# sim800.net
KiCad netlist of a schematic drawn in EAGLE
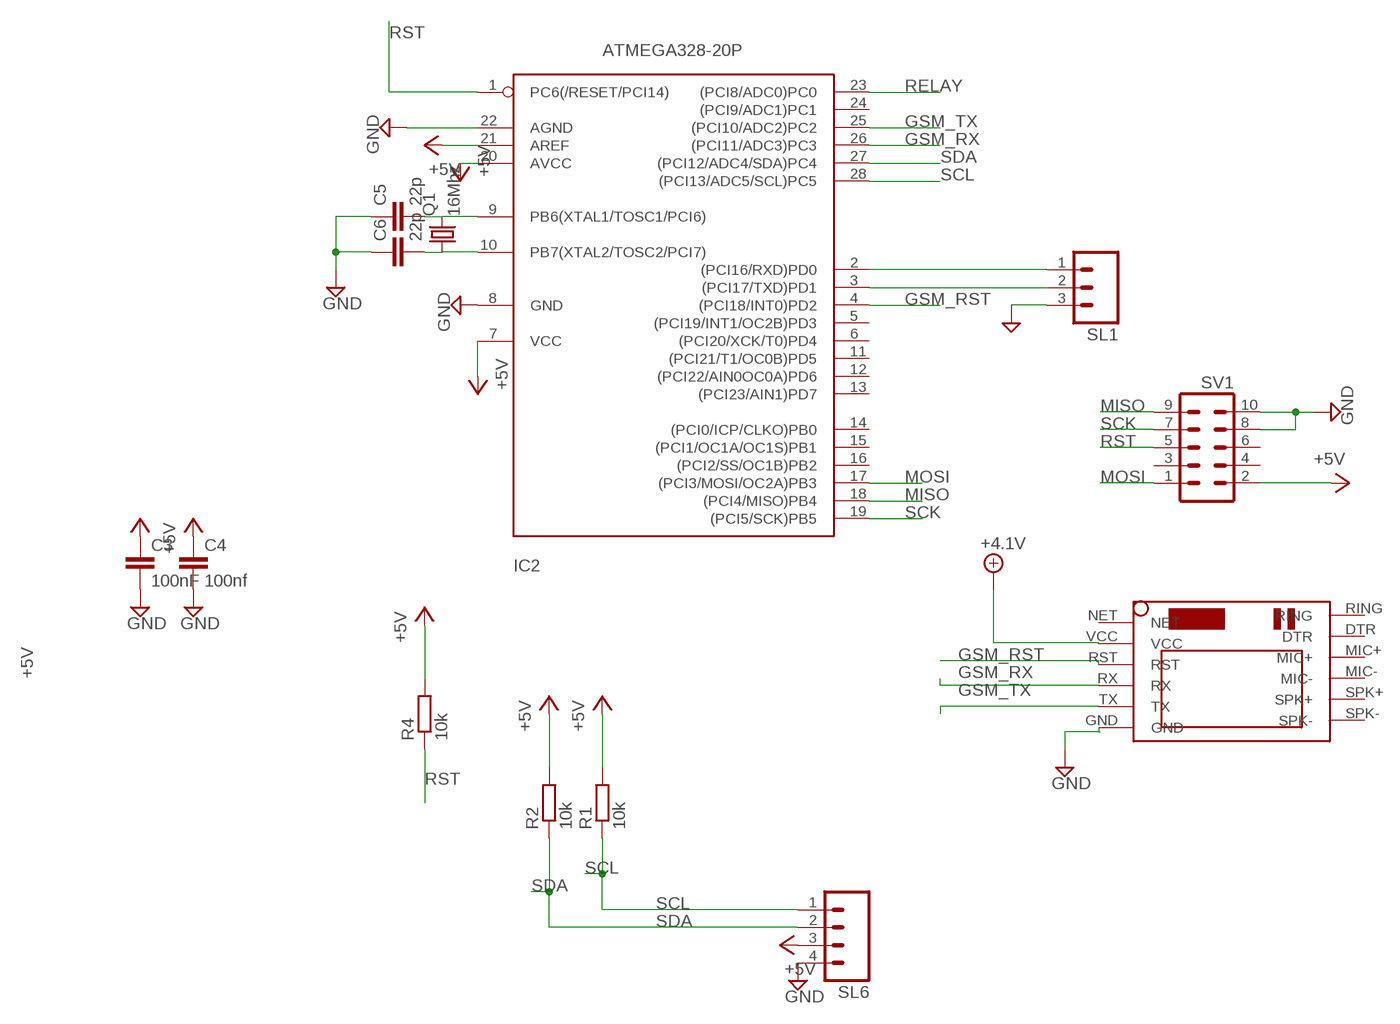
[diagram p0: schematic, sheet 1]
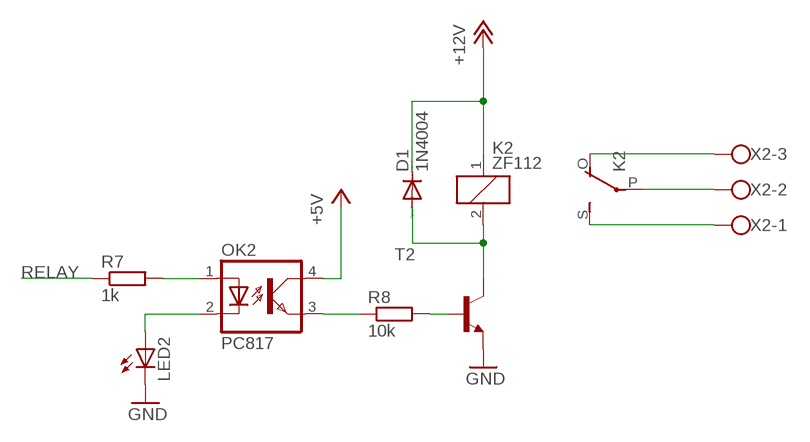
[diagram p1: schematic, sheet 2]
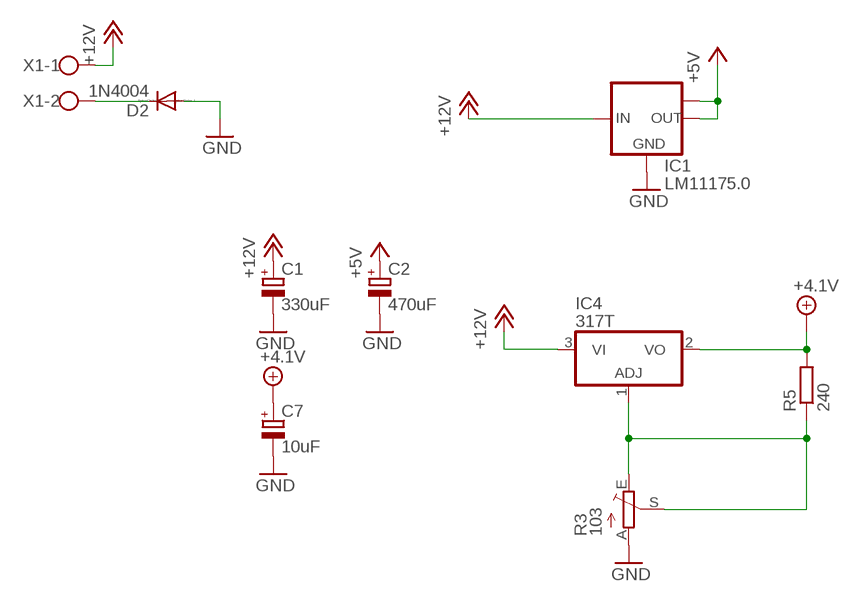
[diagram p2: schematic, sheet 3]

(export (version "E")
  (design (tool "Eeschema 10.0.6"))
  (components
    (comp (ref "C1")
      (value "330uF")
      (footprint "eagle-import:E3,5-8")
      (libsource (lib "eagle-import") (part "CPOL-EUE3.5-8"))
    )
    (comp (ref "C2")
      (value "470uF")
      (footprint "eagle-import:E3,5-8")
      (libsource (lib "eagle-import") (part "CPOL-EUE3.5-8"))
    )
    (comp (ref "C7")
      (value "10uF")
      (footprint "eagle-import:E2,5-6")
      (libsource (lib "eagle-import") (part "CPOL-EUE2.5-6"))
    )
    (comp (ref "D2")
      (value "1N4004")
      (footprint "eagle-import:DO41-10")
      (libsource (lib "eagle-import") (part "1N4004"))
    )
    (comp (ref "IC1")
      (value "LM11175.0")
      (footprint "eagle-import:SOT223")
      (libsource (lib "eagle-import") (part "LM1117MPX-5.0"))
    )
    (comp (ref "IC4")
      (value "317T")
      (footprint "eagle-import:TO220H")
      (libsource (lib "eagle-import") (part "317T"))
    )
    (comp (ref "R3")
      (value "103")
      (footprint "eagle-import:CA6V")
      (libsource (lib "eagle-import") (part "TRIM_EU-CA6V"))
    )
    (comp (ref "R5")
      (value "240")
      (footprint "eagle-import:0207_10")
      (libsource (lib "eagle-import") (part "R-EU_0207/10"))
    )
    (comp (ref "X1")
      (value "W237-102")
      (footprint "eagle-import:W237-102")
      (fields (field (name "MPN") "237-102"))
      (libsource (lib "eagle-import") (part "W237-102"))
    )
    (comp (ref "D1")
      (value "1N4004")
      (footprint "eagle-import:DO41-10")
      (libsource (lib "eagle-import") (part "1N4004"))
    )
    (comp (ref "K2")
      (value "ZF112")
      (footprint "eagle-import:ZF112")
      (libsource (lib "eagle-import") (part "ZF112"))
    )
    (comp (ref "LED2")
      (value "LED3MM")
      (footprint "eagle-import:LED3MM")
      (libsource (lib "eagle-import") (part "LED3MM"))
    )
    (comp (ref "OK2")
      (value "PC817")
      (footprint "eagle-import:DIL04")
      (fields (field (name "MPN") "PC817X4J000F"))
      (libsource (lib "eagle-import") (part "PC817"))
    )
    (comp (ref "R7")
      (value "1k")
      (footprint "eagle-import:0207_10")
      (libsource (lib "eagle-import") (part "R-EU_0207/10"))
    )
    (comp (ref "R8")
      (value "10k")
      (footprint "eagle-import:0207_10")
      (libsource (lib "eagle-import") (part "R-EU_0207/10"))
    )
    (comp (ref "T2")
      (value "-NPN-TO92-EBC")
      (footprint "eagle-import:TO92-EBC")
      (libsource (lib "eagle-import") (part "-NPN-TO92-EBC"))
    )
    (comp (ref "X2")
      (value "W237-103")
      (footprint "eagle-import:W237-103")
      (fields (field (name "MPN") "237-103"))
      (libsource (lib "eagle-import") (part "W237-103"))
    )
    (comp (ref "C3")
      (value "100nF")
      (footprint "eagle-import:C050-025X075")
      (libsource (lib "eagle-import") (part "C-EU050-025X075"))
    )
    (comp (ref "C4")
      (value "100nf")
      (footprint "eagle-import:C050-025X075")
      (libsource (lib "eagle-import") (part "C-EU050-025X075"))
    )
    (comp (ref "C5")
      (value "22p")
      (footprint "eagle-import:C025-025X050")
      (libsource (lib "eagle-import") (part "C-EU025-025X050"))
    )
    (comp (ref "C6")
      (value "22p")
      (footprint "eagle-import:C025-025X050")
      (libsource (lib "eagle-import") (part "C-EU025-025X050"))
    )
    (comp (ref "IC2")
      (value "ATMEGA328-20P")
      (footprint "eagle-import:DIL28-3")
      (libsource (lib "eagle-import") (part "ATMEGA328P-20"))
    )
    (comp (ref "Q1")
      (value "16Mhz")
      (footprint "eagle-import:HC49U-V")
      (libsource (lib "eagle-import") (part "CRYSTALHC49U-V"))
    )
    (comp (ref "R1")
      (value "10k")
      (footprint "eagle-import:0207_10")
      (libsource (lib "eagle-import") (part "R-EU_0207/10"))
    )
    (comp (ref "R2")
      (value "10k")
      (footprint "eagle-import:0207_10")
      (libsource (lib "eagle-import") (part "R-EU_0207/10"))
    )
    (comp (ref "R4")
      (value "10k")
      (footprint "eagle-import:0207_10")
      (libsource (lib "eagle-import") (part "R-EU_0207/10"))
    )
    (comp (ref "SL1")
      (value "M03")
      (footprint "eagle-import:03P")
      (libsource (lib "eagle-import") (part "M03"))
    )
    (comp (ref "SL6")
      (value "M04")
      (footprint "eagle-import:04P")
      (libsource (lib "eagle-import") (part "M04"))
    )
    (comp (ref "SV1")
      (value "ML10")
      (footprint "eagle-import:ML10")
      (libsource (lib "eagle-import") (part "ML10"))
    )
    (comp (ref "U$1")
      (value "SIM800LMODULE")
      (footprint "eagle-import:SIM800LMODULE")
      (libsource (lib "eagle-import") (part "SIM800LMODULE"))
    )
  )
  (nets
    (net (code "1") (name "+4.1V") (class "Default")
      (node (ref "C7") (pin "+") (pinfunction "+_+") (pintype "passive"))
      (node (ref "IC4") (pin "2") (pinfunction "VO_2") (pintype "passive"))
      (node (ref "R5") (pin "2") (pinfunction "2_2") (pintype "passive"))
      (node (ref "U$1") (pin "VCC") (pinfunction "VCC_VCC") (pintype "bidirectional"))
    )
    (net (code "2") (name "+5V") (class "Default")
      (node (ref "C2") (pin "+") (pinfunction "+_+") (pintype "passive"))
      (node (ref "C3") (pin "1") (pinfunction "1_1") (pintype "passive"))
      (node (ref "C4") (pin "1") (pinfunction "1_1") (pintype "passive"))
      (node (ref "IC1") (pin "2") (pinfunction "OUT_2") (pintype "passive"))
      (node (ref "IC1") (pin "TAB") (pinfunction "OUT1_TAB") (pintype "passive"))
      (node (ref "IC2") (pin "20") (pinfunction "AVCC_20") (pintype "bidirectional"))
      (node (ref "IC2") (pin "21") (pinfunction "AREF_21") (pintype "bidirectional"))
      (node (ref "IC2") (pin "7") (pinfunction "VCC_7") (pintype "bidirectional"))
      (node (ref "OK2") (pin "4") (pinfunction "COL_4") (pintype "passive"))
      (node (ref "R1") (pin "2") (pinfunction "2_2") (pintype "passive"))
      (node (ref "R2") (pin "2") (pinfunction "2_2") (pintype "passive"))
      (node (ref "R4") (pin "2") (pinfunction "2_2") (pintype "passive"))
      (node (ref "SL6") (pin "3") (pinfunction "3_3") (pintype "passive"))
      (node (ref "SV1") (pin "2") (pinfunction "2_2") (pintype "passive"))
    )
    (net (code "3") (name "+12V") (class "Default")
      (node (ref "C1") (pin "+") (pinfunction "+_+") (pintype "passive"))
      (node (ref "D1") (pin "C") (pinfunction "C_C") (pintype "passive"))
      (node (ref "IC1") (pin "3") (pinfunction "IN_3") (pintype "input"))
      (node (ref "IC4") (pin "3") (pinfunction "VI_3") (pintype "input"))
      (node (ref "K2") (pin "1") (pinfunction "1_1") (pintype "passive"))
      (node (ref "X1") (pin "1") (pinfunction "KL_1") (pintype "passive"))
    )
    (net (code "4") (name "GND") (class "Default")
      (node (ref "C1") (pin "-") (pinfunction "-_-") (pintype "passive"))
      (node (ref "C2") (pin "-") (pinfunction "-_-") (pintype "passive"))
      (node (ref "C3") (pin "2") (pinfunction "2_2") (pintype "passive"))
      (node (ref "C4") (pin "2") (pinfunction "2_2") (pintype "passive"))
      (node (ref "C5") (pin "1") (pinfunction "1_1") (pintype "passive"))
      (node (ref "C6") (pin "1") (pinfunction "1_1") (pintype "passive"))
      (node (ref "C7") (pin "-") (pinfunction "-_-") (pintype "passive"))
      (node (ref "D2") (pin "A") (pinfunction "A_A") (pintype "passive"))
      (node (ref "IC1") (pin "1") (pinfunction "GND_1") (pintype "input"))
      (node (ref "IC2") (pin "22") (pinfunction "AGND_22") (pintype "bidirectional"))
      (node (ref "IC2") (pin "8") (pinfunction "GND_8") (pintype "bidirectional"))
      (node (ref "LED2") (pin "K") (pinfunction "C_K") (pintype "passive"))
      (node (ref "R3") (pin "A") (pinfunction "A_A") (pintype "passive"))
      (node (ref "SL1") (pin "3") (pinfunction "3_3") (pintype "passive"))
      (node (ref "SL6") (pin "4") (pinfunction "4_4") (pintype "passive"))
      (node (ref "SV1") (pin "10") (pinfunction "10_10") (pintype "passive"))
      (node (ref "SV1") (pin "8") (pinfunction "8_8") (pintype "passive"))
      (node (ref "T2") (pin "E") (pinfunction "E_E") (pintype "passive"))
      (node (ref "U$1") (pin "GND") (pinfunction "GND_GND") (pintype "bidirectional"))
    )
    (net (code "5") (name "GSM_RST") (class "Default")
      (node (ref "IC2") (pin "4") (pinfunction "(PCI18/INT0)PD2_4") (pintype "bidirectional"))
      (node (ref "U$1") (pin "RST") (pinfunction "RST_RST") (pintype "bidirectional"))
    )
    (net (code "6") (name "GSM_RX") (class "Default")
      (node (ref "IC2") (pin "26") (pinfunction "(PCI11/ADC3)PC3_26") (pintype "bidirectional"))
      (node (ref "U$1") (pin "RX") (pinfunction "RX_RX") (pintype "bidirectional"))
    )
    (net (code "7") (name "GSM_TX") (class "Default")
      (node (ref "IC2") (pin "25") (pinfunction "(PCI10/ADC2)PC2_25") (pintype "bidirectional"))
      (node (ref "U$1") (pin "TX") (pinfunction "TX_TX") (pintype "bidirectional"))
    )
    (net (code "8") (name "MISO") (class "Default")
      (node (ref "IC2") (pin "18") (pinfunction "(PCI4/MISO)PB4_18") (pintype "bidirectional"))
      (node (ref "SV1") (pin "9") (pinfunction "9_9") (pintype "passive"))
    )
    (net (code "9") (name "MOSI") (class "Default")
      (node (ref "IC2") (pin "17") (pinfunction "(PCI3/MOSI/OC2A)PB3_17") (pintype "bidirectional"))
      (node (ref "SV1") (pin "1") (pinfunction "1_1") (pintype "passive"))
    )
    (net (code "10") (name "Net-(D1-PadA)") (class "Default")
      (node (ref "D1") (pin "A") (pinfunction "A_A") (pintype "passive"))
      (node (ref "K2") (pin "2") (pinfunction "2_2") (pintype "passive"))
      (node (ref "T2") (pin "C") (pinfunction "C_C") (pintype "passive"))
    )
    (net (code "11") (name "Net-(IC2-(PCI16{slash}RXD)PD0)") (class "Default")
      (node (ref "IC2") (pin "2") (pinfunction "(PCI16/RXD)PD0_2") (pintype "bidirectional"))
      (node (ref "SL1") (pin "1") (pinfunction "1_1") (pintype "passive"))
    )
    (net (code "12") (name "Net-(IC2-(PCI17{slash}TXD)PD1)") (class "Default")
      (node (ref "IC2") (pin "3") (pinfunction "(PCI17/TXD)PD1_3") (pintype "bidirectional"))
      (node (ref "SL1") (pin "2") (pinfunction "2_2") (pintype "passive"))
    )
    (net (code "13") (name "Net-(IC2-PB6(XTAL1{slash}TOSC1{slash}PCI6))") (class "Default")
      (node (ref "C5") (pin "2") (pinfunction "2_2") (pintype "passive"))
      (node (ref "IC2") (pin "9") (pinfunction "PB6(XTAL1/TOSC1/PCI6)_9") (pintype "bidirectional"))
      (node (ref "Q1") (pin "2") (pinfunction "2_2") (pintype "passive"))
    )
    (net (code "14") (name "Net-(IC2-PB7(XTAL2{slash}TOSC2{slash}PCI7))") (class "Default")
      (node (ref "C6") (pin "2") (pinfunction "2_2") (pintype "passive"))
      (node (ref "IC2") (pin "10") (pinfunction "PB7(XTAL2/TOSC2/PCI7)_10") (pintype "bidirectional"))
      (node (ref "Q1") (pin "1") (pinfunction "1_1") (pintype "passive"))
    )
    (net (code "15") (name "Net-(IC4-ADJ)") (class "Default")
      (node (ref "IC4") (pin "1") (pinfunction "ADJ_1") (pintype "input"))
      (node (ref "R3") (pin "E") (pinfunction "E_E") (pintype "passive"))
      (node (ref "R3") (pin "S") (pinfunction "S_S") (pintype "passive"))
      (node (ref "R5") (pin "1") (pinfunction "1_1") (pintype "passive"))
    )
    (net (code "16") (name "Net-(OK2-A)") (class "Default")
      (node (ref "OK2") (pin "1") (pinfunction "A_1") (pintype "passive"))
      (node (ref "R7") (pin "2") (pinfunction "2_2") (pintype "passive"))
    )
    (net (code "17") (name "Net-(OK2-C)") (class "Default")
      (node (ref "LED2") (pin "A") (pinfunction "A_A") (pintype "passive"))
      (node (ref "OK2") (pin "2") (pinfunction "C_2") (pintype "passive"))
    )
    (net (code "18") (name "Net-(OK2-EMIT)") (class "Default")
      (node (ref "OK2") (pin "3") (pinfunction "EMIT_3") (pintype "passive"))
      (node (ref "R8") (pin "1") (pinfunction "1_1") (pintype "passive"))
    )
    (net (code "19") (name "Net-(R8-Pad2)") (class "Default")
      (node (ref "R8") (pin "2") (pinfunction "2_2") (pintype "passive"))
      (node (ref "T2") (pin "B") (pinfunction "B_B") (pintype "passive"))
    )
    (net (code "20") (name "Net-(X1B-KL)") (class "Default")
      (node (ref "D2") (pin "C") (pinfunction "C_C") (pintype "passive"))
      (node (ref "X1") (pin "2") (pinfunction "KL_2") (pintype "passive"))
    )
    (net (code "21") (name "Net-(X2A-KL)") (class "Default")
      (node (ref "K2") (pin "S") (pinfunction "S_S") (pintype "passive"))
      (node (ref "X2") (pin "1") (pinfunction "KL_1") (pintype "passive"))
    )
    (net (code "22") (name "Net-(X2B-KL)") (class "Default")
      (node (ref "K2") (pin "P") (pinfunction "P_P") (pintype "passive"))
      (node (ref "X2") (pin "2") (pinfunction "KL_2") (pintype "passive"))
    )
    (net (code "23") (name "Net-(X2C-KL)") (class "Default")
      (node (ref "K2") (pin "O") (pinfunction "O_O") (pintype "passive"))
      (node (ref "X2") (pin "3") (pinfunction "KL_3") (pintype "passive"))
    )
    (net (code "24") (name "RELAY") (class "Default")
      (node (ref "IC2") (pin "23") (pinfunction "(PCI8/ADC0)PC0_23") (pintype "bidirectional"))
      (node (ref "R7") (pin "1") (pinfunction "1_1") (pintype "passive"))
    )
    (net (code "25") (name "RST") (class "Default")
      (node (ref "IC2") (pin "1") (pinfunction "PC6(/RESET/PCI14)_1") (pintype "bidirectional"))
      (node (ref "R4") (pin "1") (pinfunction "1_1") (pintype "passive"))
      (node (ref "SV1") (pin "5") (pinfunction "5_5") (pintype "passive"))
    )
    (net (code "26") (name "SCK") (class "Default")
      (node (ref "IC2") (pin "19") (pinfunction "(PCI5/SCK)PB5_19") (pintype "bidirectional"))
      (node (ref "SV1") (pin "7") (pinfunction "7_7") (pintype "passive"))
    )
    (net (code "27") (name "SCL") (class "Default")
      (node (ref "IC2") (pin "28") (pinfunction "(PCI13/ADC5/SCL)PC5_28") (pintype "bidirectional"))
      (node (ref "R1") (pin "1") (pinfunction "1_1") (pintype "passive"))
      (node (ref "SL6") (pin "1") (pinfunction "1_1") (pintype "passive"))
    )
    (net (code "28") (name "SDA") (class "Default")
      (node (ref "IC2") (pin "27") (pinfunction "(PCI12/ADC4/SDA)PC4_27") (pintype "bidirectional"))
      (node (ref "R2") (pin "1") (pinfunction "1_1") (pintype "passive"))
      (node (ref "SL6") (pin "2") (pinfunction "2_2") (pintype "passive"))
    )
    (net (code "29") (name "unconnected-(IC2-(PCI0{slash}ICP{slash}CLKO)PB0-Pad14)") (class "Default")
      (node (ref "IC2") (pin "14") (pinfunction "(PCI0/ICP/CLKO)PB0_14") (pintype "bidirectional"))
    )
    (net (code "30") (name "unconnected-(IC2-(PCI1{slash}OC1A{slash}OC1S)PB1-Pad15)") (class "Default")
      (node (ref "IC2") (pin "15") (pinfunction "(PCI1/OC1A/OC1S)PB1_15") (pintype "bidirectional"))
    )
    (net (code "31") (name "unconnected-(IC2-(PCI2{slash}SS{slash}OC1B)PB2-Pad16)") (class "Default")
      (node (ref "IC2") (pin "16") (pinfunction "(PCI2/SS/OC1B)PB2_16") (pintype "bidirectional"))
    )
    (net (code "32") (name "unconnected-(IC2-(PCI9{slash}ADC1)PC1-Pad24)") (class "Default")
      (node (ref "IC2") (pin "24") (pinfunction "(PCI9/ADC1)PC1_24") (pintype "bidirectional"))
    )
    (net (code "33") (name "unconnected-(IC2-(PCI19{slash}INT1{slash}OC2B)PD3-Pad5)") (class "Default")
      (node (ref "IC2") (pin "5") (pinfunction "(PCI19/INT1/OC2B)PD3_5") (pintype "bidirectional"))
    )
    (net (code "34") (name "unconnected-(IC2-(PCI20{slash}XCK{slash}T0)PD4-Pad6)") (class "Default")
      (node (ref "IC2") (pin "6") (pinfunction "(PCI20/XCK/T0)PD4_6") (pintype "bidirectional"))
    )
    (net (code "35") (name "unconnected-(IC2-(PCI21{slash}T1{slash}OC0B)PD5-Pad11)") (class "Default")
      (node (ref "IC2") (pin "11") (pinfunction "(PCI21/T1/OC0B)PD5_11") (pintype "bidirectional"))
    )
    (net (code "36") (name "unconnected-(IC2-(PCI22{slash}AIN0OC0A)PD6-Pad12)") (class "Default")
      (node (ref "IC2") (pin "12") (pinfunction "(PCI22/AIN0OC0A)PD6_12") (pintype "bidirectional"))
    )
    (net (code "37") (name "unconnected-(IC2-(PCI23{slash}AIN1)PD7-Pad13)") (class "Default")
      (node (ref "IC2") (pin "13") (pinfunction "(PCI23/AIN1)PD7_13") (pintype "bidirectional"))
    )
    (net (code "38") (name "unconnected-(SV1-Pad3)") (class "Default")
      (node (ref "SV1") (pin "3") (pinfunction "3_3") (pintype "passive"))
    )
    (net (code "39") (name "unconnected-(SV1-Pad4)") (class "Default")
      (node (ref "SV1") (pin "4") (pinfunction "4_4") (pintype "passive"))
    )
    (net (code "40") (name "unconnected-(SV1-Pad6)") (class "Default")
      (node (ref "SV1") (pin "6") (pinfunction "6_6") (pintype "passive"))
    )
    (net (code "41") (name "unconnected-(U$1-PadDTR)") (class "Default")
      (node (ref "U$1") (pin "DTR") (pinfunction "DTR_DTR") (pintype "bidirectional"))
    )
    (net (code "42") (name "unconnected-(U$1-PadMIC+)") (class "Default")
      (node (ref "U$1") (pin "MIC+") (pinfunction "MIC+_MIC+") (pintype "bidirectional"))
    )
    (net (code "43") (name "unconnected-(U$1-PadMIC-)") (class "Default")
      (node (ref "U$1") (pin "MIC-") (pinfunction "MIC-_MIC-") (pintype "bidirectional"))
    )
    (net (code "44") (name "unconnected-(U$1-PadNET)") (class "Default")
      (node (ref "U$1") (pin "NET") (pinfunction "NET_NET") (pintype "bidirectional"))
    )
    (net (code "45") (name "unconnected-(U$1-PadRING)") (class "Default")
      (node (ref "U$1") (pin "RING") (pinfunction "RING_RING") (pintype "bidirectional"))
    )
    (net (code "46") (name "unconnected-(U$1-PadSPK+)") (class "Default")
      (node (ref "U$1") (pin "SPK+") (pinfunction "SPK+_SPK+") (pintype "bidirectional"))
    )
    (net (code "47") (name "unconnected-(U$1-PadSPK-)") (class "Default")
      (node (ref "U$1") (pin "SPK-") (pinfunction "SPK-_SPK-") (pintype "bidirectional"))
    )
  )
)
